# motor_board_headers.net
KiCad netlist of a schematic drawn in EAGLE
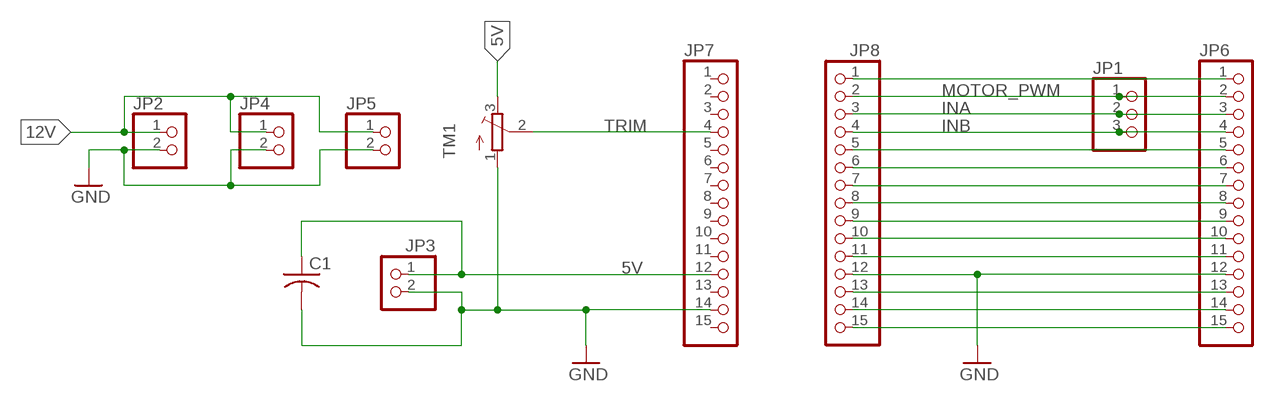
[diagram p0: schematic, sheet 1]

(export (version "E")
  (design (tool "Eeschema 10.0.6"))
  (components
    (comp (ref "C1")
      (value "C-US025-060X050")
      (footprint "eagle-import:C025-060X050")
      (libsource (lib "eagle-import") (part "C-US025-060X050"))
    )
    (comp (ref "JP1")
      (value "PINHD-1X3")
      (footprint "eagle-import:1X03")
      (libsource (lib "eagle-import") (part "PINHD-1X3"))
    )
    (comp (ref "JP2")
      (value "PINHD-1X2")
      (footprint "eagle-import:1X02")
      (libsource (lib "eagle-import") (part "PINHD-1X2"))
    )
    (comp (ref "JP3")
      (value "PINHD-1X2")
      (footprint "eagle-import:1X02")
      (libsource (lib "eagle-import") (part "PINHD-1X2"))
    )
    (comp (ref "JP4")
      (value "PINHD-1X2")
      (footprint "eagle-import:1X02")
      (libsource (lib "eagle-import") (part "PINHD-1X2"))
    )
    (comp (ref "JP5")
      (value "PINHD-1X2")
      (footprint "eagle-import:1X02")
      (libsource (lib "eagle-import") (part "PINHD-1X2"))
    )
    (comp (ref "JP6")
      (value "PINHD-1X15")
      (footprint "eagle-import:1X15")
      (libsource (lib "eagle-import") (part "PINHD-1X15"))
    )
    (comp (ref "JP7")
      (value "PINHD-1X15")
      (footprint "eagle-import:1X15")
      (libsource (lib "eagle-import") (part "PINHD-1X15"))
    )
    (comp (ref "JP8")
      (value "PINHD-1X15")
      (footprint "eagle-import:1X15")
      (libsource (lib "eagle-import") (part "PINHD-1X15"))
    )
    (comp (ref "TM1")
      (value "TRIMPOT3386")
      (footprint "eagle-import:TRIM-3386")
      (libsource (lib "eagle-import") (part "TRIMPOT3386"))
    )
  )
  (nets
    (net (code "1") (name "/INA") (class "Default")
      (node (ref "JP1") (pin "2") (pinfunction "2_2") (pintype "passive"))
      (node (ref "JP6") (pin "3") (pinfunction "3_3") (pintype "passive"))
      (node (ref "JP8") (pin "3") (pinfunction "3_3") (pintype "passive"))
    )
    (net (code "2") (name "/INB") (class "Default")
      (node (ref "JP1") (pin "3") (pinfunction "3_3") (pintype "passive"))
      (node (ref "JP6") (pin "4") (pinfunction "4_4") (pintype "passive"))
      (node (ref "JP8") (pin "4") (pinfunction "4_4") (pintype "passive"))
    )
    (net (code "3") (name "/MOTOR_PWM") (class "Default")
      (node (ref "JP1") (pin "1") (pinfunction "1_1") (pintype "passive"))
      (node (ref "JP6") (pin "2") (pinfunction "2_2") (pintype "passive"))
      (node (ref "JP8") (pin "2") (pinfunction "2_2") (pintype "passive"))
    )
    (net (code "4") (name "/TRIM") (class "Default")
      (node (ref "JP7") (pin "4") (pinfunction "4_4") (pintype "passive"))
      (node (ref "TM1") (pin "2") (pinfunction "S_2") (pintype "passive"))
    )
    (net (code "5") (name "5V") (class "Default")
      (node (ref "C1") (pin "1") (pinfunction "1_1") (pintype "passive"))
      (node (ref "JP3") (pin "1") (pinfunction "1_1") (pintype "passive"))
      (node (ref "JP7") (pin "12") (pinfunction "12_12") (pintype "passive"))
      (node (ref "TM1") (pin "3") (pinfunction "E_3") (pintype "passive"))
    )
    (net (code "6") (name "12V") (class "Default")
      (node (ref "JP2") (pin "1") (pinfunction "1_1") (pintype "passive"))
      (node (ref "JP4") (pin "1") (pinfunction "1_1") (pintype "passive"))
      (node (ref "JP5") (pin "1") (pinfunction "1_1") (pintype "passive"))
    )
    (net (code "7") (name "GND") (class "Default")
      (node (ref "C1") (pin "2") (pinfunction "2_2") (pintype "passive"))
      (node (ref "JP2") (pin "2") (pinfunction "2_2") (pintype "passive"))
      (node (ref "JP3") (pin "2") (pinfunction "2_2") (pintype "passive"))
      (node (ref "JP4") (pin "2") (pinfunction "2_2") (pintype "passive"))
      (node (ref "JP5") (pin "2") (pinfunction "2_2") (pintype "passive"))
      (node (ref "JP6") (pin "12") (pinfunction "12_12") (pintype "passive"))
      (node (ref "JP7") (pin "14") (pinfunction "14_14") (pintype "passive"))
      (node (ref "JP8") (pin "12") (pinfunction "12_12") (pintype "passive"))
      (node (ref "TM1") (pin "1") (pinfunction "A_1") (pintype "passive"))
    )
    (net (code "8") (name "Net-(JP6-Pad1)") (class "Default")
      (node (ref "JP6") (pin "1") (pinfunction "1_1") (pintype "passive"))
      (node (ref "JP8") (pin "1") (pinfunction "1_1") (pintype "passive"))
    )
    (net (code "9") (name "Net-(JP6-Pad5)") (class "Default")
      (node (ref "JP6") (pin "5") (pinfunction "5_5") (pintype "passive"))
      (node (ref "JP8") (pin "5") (pinfunction "5_5") (pintype "passive"))
    )
    (net (code "10") (name "Net-(JP6-Pad6)") (class "Default")
      (node (ref "JP6") (pin "6") (pinfunction "6_6") (pintype "passive"))
      (node (ref "JP8") (pin "6") (pinfunction "6_6") (pintype "passive"))
    )
    (net (code "11") (name "Net-(JP6-Pad7)") (class "Default")
      (node (ref "JP6") (pin "7") (pinfunction "7_7") (pintype "passive"))
      (node (ref "JP8") (pin "7") (pinfunction "7_7") (pintype "passive"))
    )
    (net (code "12") (name "Net-(JP6-Pad8)") (class "Default")
      (node (ref "JP6") (pin "8") (pinfunction "8_8") (pintype "passive"))
      (node (ref "JP8") (pin "8") (pinfunction "8_8") (pintype "passive"))
    )
    (net (code "13") (name "Net-(JP6-Pad9)") (class "Default")
      (node (ref "JP6") (pin "9") (pinfunction "9_9") (pintype "passive"))
      (node (ref "JP8") (pin "9") (pinfunction "9_9") (pintype "passive"))
    )
    (net (code "14") (name "Net-(JP6-Pad10)") (class "Default")
      (node (ref "JP6") (pin "10") (pinfunction "10_10") (pintype "passive"))
      (node (ref "JP8") (pin "10") (pinfunction "10_10") (pintype "passive"))
    )
    (net (code "15") (name "Net-(JP6-Pad11)") (class "Default")
      (node (ref "JP6") (pin "11") (pinfunction "11_11") (pintype "passive"))
      (node (ref "JP8") (pin "11") (pinfunction "11_11") (pintype "passive"))
    )
    (net (code "16") (name "Net-(JP6-Pad13)") (class "Default")
      (node (ref "JP6") (pin "13") (pinfunction "13_13") (pintype "passive"))
      (node (ref "JP8") (pin "13") (pinfunction "13_13") (pintype "passive"))
    )
    (net (code "17") (name "Net-(JP6-Pad14)") (class "Default")
      (node (ref "JP6") (pin "14") (pinfunction "14_14") (pintype "passive"))
      (node (ref "JP8") (pin "14") (pinfunction "14_14") (pintype "passive"))
    )
    (net (code "18") (name "Net-(JP6-Pad15)") (class "Default")
      (node (ref "JP6") (pin "15") (pinfunction "15_15") (pintype "passive"))
      (node (ref "JP8") (pin "15") (pinfunction "15_15") (pintype "passive"))
    )
    (net (code "19") (name "unconnected-(JP7-Pad1)") (class "Default")
      (node (ref "JP7") (pin "1") (pinfunction "1_1") (pintype "passive"))
    )
    (net (code "20") (name "unconnected-(JP7-Pad2)") (class "Default")
      (node (ref "JP7") (pin "2") (pinfunction "2_2") (pintype "passive"))
    )
    (net (code "21") (name "unconnected-(JP7-Pad3)") (class "Default")
      (node (ref "JP7") (pin "3") (pinfunction "3_3") (pintype "passive"))
    )
    (net (code "22") (name "unconnected-(JP7-Pad5)") (class "Default")
      (node (ref "JP7") (pin "5") (pinfunction "5_5") (pintype "passive"))
    )
    (net (code "23") (name "unconnected-(JP7-Pad6)") (class "Default")
      (node (ref "JP7") (pin "6") (pinfunction "6_6") (pintype "passive"))
    )
    (net (code "24") (name "unconnected-(JP7-Pad7)") (class "Default")
      (node (ref "JP7") (pin "7") (pinfunction "7_7") (pintype "passive"))
    )
    (net (code "25") (name "unconnected-(JP7-Pad8)") (class "Default")
      (node (ref "JP7") (pin "8") (pinfunction "8_8") (pintype "passive"))
    )
    (net (code "26") (name "unconnected-(JP7-Pad9)") (class "Default")
      (node (ref "JP7") (pin "9") (pinfunction "9_9") (pintype "passive"))
    )
    (net (code "27") (name "unconnected-(JP7-Pad10)") (class "Default")
      (node (ref "JP7") (pin "10") (pinfunction "10_10") (pintype "passive"))
    )
    (net (code "28") (name "unconnected-(JP7-Pad11)") (class "Default")
      (node (ref "JP7") (pin "11") (pinfunction "11_11") (pintype "passive"))
    )
    (net (code "29") (name "unconnected-(JP7-Pad13)") (class "Default")
      (node (ref "JP7") (pin "13") (pinfunction "13_13") (pintype "passive"))
    )
    (net (code "30") (name "unconnected-(JP7-Pad15)") (class "Default")
      (node (ref "JP7") (pin "15") (pinfunction "15_15") (pintype "passive"))
    )
  )
)
